# ESP32-Cam-Pico-V1.net
KiCad netlist of a schematic drawn in EAGLE
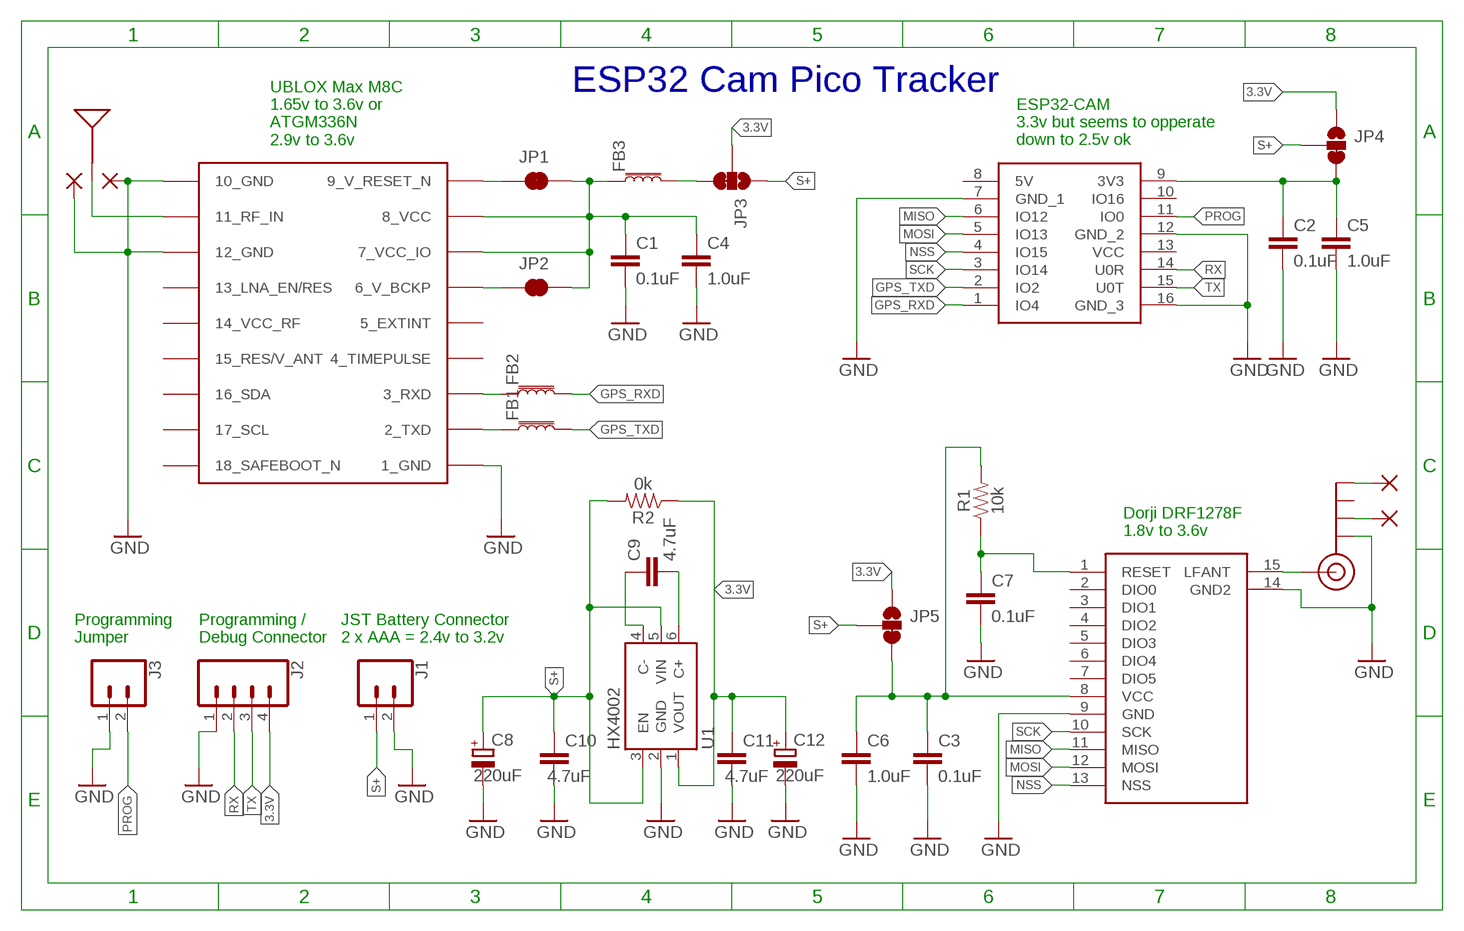
[diagram p0: schematic, sheet 1]

(export (version "E")
  (design (tool "Eeschema 10.0.6"))
  (components
    (comp (ref "C1")
      (value "0.1uF")
      (footprint "eagle-import:0402")
      (libsource (lib "eagle-import") (part "0.1UF-0402-6.3V-10%-X7R"))
    )
    (comp (ref "C2")
      (value "0.1uF")
      (footprint "eagle-import:0402")
      (libsource (lib "eagle-import") (part "0.1UF-0402-6.3V-10%-X7R"))
    )
    (comp (ref "C3")
      (value "0.1uF")
      (footprint "eagle-import:0402")
      (libsource (lib "eagle-import") (part "0.1UF-0402-6.3V-10%-X7R"))
    )
    (comp (ref "C4")
      (value "1.0uF")
      (footprint "eagle-import:0402")
      (libsource (lib "eagle-import") (part "1.0UF-0402-16V-10%"))
    )
    (comp (ref "C5")
      (value "1.0uF")
      (footprint "eagle-import:0402")
      (libsource (lib "eagle-import") (part "1.0UF-0402-16V-10%"))
    )
    (comp (ref "C6")
      (value "1.0uF")
      (footprint "eagle-import:0402")
      (libsource (lib "eagle-import") (part "1.0UF-0402-16V-10%"))
    )
    (comp (ref "C7")
      (value "0.1uF")
      (footprint "eagle-import:0402")
      (libsource (lib "eagle-import") (part "0.1UF-0402-6.3V-10%-X7R"))
    )
    (comp (ref "C8")
      (value "220uF")
      (footprint "eagle-import:SMC_C")
      (libsource (lib "eagle-import") (part "CPOL-EUSMCC"))
    )
    (comp (ref "C9")
      (value "4.7uF")
      (footprint "eagle-import:0402")
      (libsource (lib "eagle-import") (part "1.0UF-0402-16V-10%"))
    )
    (comp (ref "C10")
      (value "4.7uF")
      (footprint "eagle-import:0402")
      (libsource (lib "eagle-import") (part "1.0UF-0402-16V-10%"))
    )
    (comp (ref "C11")
      (value "4.7uF")
      (footprint "eagle-import:0402")
      (libsource (lib "eagle-import") (part "1.0UF-0402-16V-10%"))
    )
    (comp (ref "C12")
      (value "220uF")
      (footprint "eagle-import:SMC_C")
      (libsource (lib "eagle-import") (part "CPOL-EUSMCC"))
    )
    (comp (ref "FB1")
      (value "FERRITE_BEAD-120_OHM-0402")
      (footprint "eagle-import:0402")
      (fields (field (name "MFG_PART") "BLM15HB121SN1D"))
      (libsource (lib "eagle-import") (part "FERRITE_BEAD-120_OHM-0402"))
    )
    (comp (ref "FB2")
      (value "FERRITE_BEAD-120_OHM-0402")
      (footprint "eagle-import:0402")
      (fields (field (name "MFG_PART") "BLM15HB121SN1D"))
      (libsource (lib "eagle-import") (part "FERRITE_BEAD-120_OHM-0402"))
    )
    (comp (ref "FB3")
      (value "FERRITE_BEAD-120_OHM-0402")
      (footprint "eagle-import:0402")
      (fields (field (name "MFG_PART") "BLM15HB121SN1D"))
      (libsource (lib "eagle-import") (part "FERRITE_BEAD-120_OHM-0402"))
    )
    (comp (ref "IC1")
      (value "ESP32-CAM")
      (footprint "eagle-import:ESP32CAM")
      (libsource (lib "eagle-import") (part "ESP32-CAM"))
    )
    (comp (ref "J$1")
      (value "SMA_EDGE")
      (footprint "eagle-import:SMA-EDGE")
      (libsource (lib "eagle-import") (part "SMA_EDGE"))
    )
    (comp (ref "J1")
      (value "CONN_02JST-PTH-2-KIT")
      (footprint "eagle-import:JST-2-PTH-KIT")
      (libsource (lib "eagle-import") (part "CONN_02JST-PTH-2-KIT"))
    )
    (comp (ref "J2")
      (value "CONN_04LOCK")
      (footprint "eagle-import:1X04_LOCK")
      (libsource (lib "eagle-import") (part "CONN_04LOCK"))
    )
    (comp (ref "J3")
      (value "CONN_02LOCK")
      (footprint "eagle-import:1X02_LOCK")
      (libsource (lib "eagle-import") (part "CONN_02LOCK"))
    )
    (comp (ref "JP1")
      (value "JUMPER-SMT_2_NC_TRACE_NO-SILK")
      (footprint "eagle-import:SMT-JUMPER_2_NC_TRACE_NO-SILK")
      (libsource (lib "eagle-import") (part "JUMPER-SMT_2_NC_TRACE_NO-SILK"))
    )
    (comp (ref "JP2")
      (value "JUMPER-SMT_2_NC_TRACE_NO-SILK")
      (footprint "eagle-import:SMT-JUMPER_2_NC_TRACE_NO-SILK")
      (libsource (lib "eagle-import") (part "JUMPER-SMT_2_NC_TRACE_NO-SILK"))
    )
    (comp (ref "JP3")
      (value "JUMPER-SMT_3_1-NC_TRACE_SILK")
      (footprint "eagle-import:SMT-JUMPER_3_1-NC_TRACE_SILK")
      (libsource (lib "eagle-import") (part "JUMPER-SMT_3_1-NC_TRACE_SILK"))
    )
    (comp (ref "JP4")
      (value "JUMPER-SMT_3_1-NC_TRACE_SILK")
      (footprint "eagle-import:SMT-JUMPER_3_1-NC_TRACE_SILK")
      (libsource (lib "eagle-import") (part "JUMPER-SMT_3_1-NC_TRACE_SILK"))
    )
    (comp (ref "JP5")
      (value "JUMPER-SMT_3_1-NC_TRACE_SILK")
      (footprint "eagle-import:SMT-JUMPER_3_1-NC_TRACE_SILK")
      (libsource (lib "eagle-import") (part "JUMPER-SMT_3_1-NC_TRACE_SILK"))
    )
    (comp (ref "PAD1")
      (value "1,6/0,8")
      (footprint "eagle-import:1,6_0,8")
      (libsource (lib "eagle-import") (part "1,6/0,8"))
    )
    (comp (ref "PAD2")
      (value "1,6/0,8")
      (footprint "eagle-import:1,6_0,8")
      (libsource (lib "eagle-import") (part "1,6/0,8"))
    )
    (comp (ref "PAD3")
      (value "1,6/0,8")
      (footprint "eagle-import:1,6_0,8")
      (libsource (lib "eagle-import") (part "1,6/0,8"))
    )
    (comp (ref "PAD4")
      (value "1,6/0,8")
      (footprint "eagle-import:1,6_0,8")
      (libsource (lib "eagle-import") (part "1,6/0,8"))
    )
    (comp (ref "R1")
      (value "10k")
      (footprint "eagle-import:0402")
      (libsource (lib "eagle-import") (part "10KOHM-0402-1/16W-1%"))
    )
    (comp (ref "R2")
      (value "0k")
      (footprint "eagle-import:0402")
      (libsource (lib "eagle-import") (part "10KOHM-0402-1/16W-1%"))
    )
    (comp (ref "U$1")
      (value "MAX-M8")
      (footprint "eagle-import:MAX-M8")
      (libsource (lib "eagle-import") (part "MAX-M8"))
    )
    (comp (ref "U$2")
      (value "1.575GHz")
      (footprint "eagle-import:ANT-GPS-2X7MM")
      (libsource (lib "eagle-import") (part "ANTENNAGPS-2X7MM"))
    )
    (comp (ref "U$3")
      (value "DRF1278F_2")
      (footprint "eagle-import:DRF1278F_2")
      (libsource (lib "eagle-import") (part "DRF1278F_2"))
    )
    (comp (ref "U1")
      (value "HX4002")
      (footprint "eagle-import:SOT23-6")
      (libsource (lib "eagle-import") (part "CE021SOT-23"))
    )
  )
  (nets
    (net (code "1") (name "3.3V") (class "Default")
      (node (ref "C11") (pin "1") (pinfunction "1_1") (pintype "passive"))
      (node (ref "C12") (pin "+") (pinfunction "+_+") (pintype "passive"))
      (node (ref "C2") (pin "1") (pinfunction "1_1") (pintype "passive"))
      (node (ref "C5") (pin "1") (pinfunction "1_1") (pintype "passive"))
      (node (ref "IC1") (pin "9") (pinfunction "3V3_9") (pintype "bidirectional"))
      (node (ref "J2") (pin "4") (pinfunction "4_4") (pintype "passive"))
      (node (ref "JP3") (pin "2") (pinfunction "2_2") (pintype "passive"))
      (node (ref "JP4") (pin "1") (pinfunction "1_1") (pintype "passive"))
      (node (ref "JP4") (pin "3") (pinfunction "3_3") (pintype "passive"))
      (node (ref "JP5") (pin "1") (pinfunction "1_1") (pintype "passive"))
      (node (ref "R2") (pin "1") (pinfunction "1_1") (pintype "passive"))
      (node (ref "U1") (pin "1") (pinfunction "VOUT_1") (pintype "bidirectional"))
    )
    (net (code "2") (name "GND") (class "Default")
      (node (ref "C1") (pin "2") (pinfunction "2_2") (pintype "passive"))
      (node (ref "C10") (pin "2") (pinfunction "2_2") (pintype "passive"))
      (node (ref "C11") (pin "2") (pinfunction "2_2") (pintype "passive"))
      (node (ref "C12") (pin "-") (pinfunction "-_-") (pintype "passive"))
      (node (ref "C2") (pin "2") (pinfunction "2_2") (pintype "passive"))
      (node (ref "C3") (pin "2") (pinfunction "2_2") (pintype "passive"))
      (node (ref "C4") (pin "2") (pinfunction "2_2") (pintype "passive"))
      (node (ref "C5") (pin "2") (pinfunction "2_2") (pintype "passive"))
      (node (ref "C6") (pin "2") (pinfunction "2_2") (pintype "passive"))
      (node (ref "C7") (pin "2") (pinfunction "2_2") (pintype "passive"))
      (node (ref "C8") (pin "-") (pinfunction "-_-") (pintype "passive"))
      (node (ref "IC1") (pin "12") (pinfunction "GND_2_12") (pintype "bidirectional"))
      (node (ref "IC1") (pin "16") (pinfunction "GND_3_16") (pintype "bidirectional"))
      (node (ref "IC1") (pin "7") (pinfunction "GND_1_7") (pintype "bidirectional"))
      (node (ref "J$1") (pin "GND@0") (pinfunction "GND_GND@0") (pintype "bidirectional"))
      (node (ref "J1") (pin "2") (pinfunction "2_2") (pintype "passive"))
      (node (ref "J2") (pin "1") (pinfunction "1_1") (pintype "passive"))
      (node (ref "J3") (pin "1") (pinfunction "1_1") (pintype "passive"))
      (node (ref "PAD1") (pin "1") (pinfunction "P_1") (pintype "passive"))
      (node (ref "PAD2") (pin "1") (pinfunction "P_1") (pintype "passive"))
      (node (ref "U$1") (pin "10_GND") (pinfunction "10_GND_10_GND") (pintype "power_in"))
      (node (ref "U$1") (pin "12_GND") (pinfunction "12_GND_12_GND") (pintype "power_in"))
      (node (ref "U$1") (pin "1_GND") (pinfunction "1_GND_1_GND") (pintype "power_in"))
      (node (ref "U$3") (pin "14") (pinfunction "GND2_14") (pintype "bidirectional"))
      (node (ref "U$3") (pin "9") (pinfunction "GND_9") (pintype "bidirectional"))
      (node (ref "U1") (pin "2") (pinfunction "GND_2") (pintype "bidirectional"))
    )
    (net (code "3") (name "GPS_RXD") (class "Default")
      (node (ref "FB2") (pin "2") (pinfunction "2_2") (pintype "passive"))
      (node (ref "IC1") (pin "1") (pinfunction "IO4_1") (pintype "bidirectional"))
    )
    (net (code "4") (name "GPS_TXD") (class "Default")
      (node (ref "FB1") (pin "2") (pinfunction "2_2") (pintype "passive"))
      (node (ref "IC1") (pin "2") (pinfunction "IO2_2") (pintype "bidirectional"))
    )
    (net (code "5") (name "MISO") (class "Default")
      (node (ref "IC1") (pin "6") (pinfunction "IO12_6") (pintype "bidirectional"))
      (node (ref "U$3") (pin "11") (pinfunction "MISO_11") (pintype "bidirectional"))
    )
    (net (code "6") (name "MOSI") (class "Default")
      (node (ref "IC1") (pin "5") (pinfunction "IO13_5") (pintype "bidirectional"))
      (node (ref "U$3") (pin "12") (pinfunction "MOSI_12") (pintype "bidirectional"))
    )
    (net (code "7") (name "NSS") (class "Default")
      (node (ref "IC1") (pin "4") (pinfunction "IO15_4") (pintype "bidirectional"))
      (node (ref "U$3") (pin "13") (pinfunction "NSS_13") (pintype "bidirectional"))
    )
    (net (code "8") (name "Net-(C1-Pad1)") (class "Default")
      (node (ref "C1") (pin "1") (pinfunction "1_1") (pintype "passive"))
      (node (ref "C4") (pin "1") (pinfunction "1_1") (pintype "passive"))
      (node (ref "FB3") (pin "1") (pinfunction "1_1") (pintype "passive"))
      (node (ref "JP1") (pin "2") (pinfunction "2_2") (pintype "passive"))
      (node (ref "JP2") (pin "2") (pinfunction "2_2") (pintype "passive"))
      (node (ref "U$1") (pin "7_VCC_IO") (pinfunction "7_VCC_IO_7_VCC_IO") (pintype "power_in"))
      (node (ref "U$1") (pin "8_VCC") (pinfunction "8_VCC_8_VCC") (pintype "power_in"))
    )
    (net (code "9") (name "Net-(FB1-Pad1)") (class "Default")
      (node (ref "FB1") (pin "1") (pinfunction "1_1") (pintype "passive"))
      (node (ref "U$1") (pin "2_TXD") (pinfunction "2_TXD_2_TXD") (pintype "bidirectional"))
    )
    (net (code "10") (name "Net-(FB2-Pad1)") (class "Default")
      (node (ref "FB2") (pin "1") (pinfunction "1_1") (pintype "passive"))
      (node (ref "U$1") (pin "3_RXD") (pinfunction "3_RXD_3_RXD") (pintype "bidirectional"))
    )
    (net (code "11") (name "Net-(FB3-Pad2)") (class "Default")
      (node (ref "FB3") (pin "2") (pinfunction "2_2") (pintype "passive"))
      (node (ref "JP3") (pin "3") (pinfunction "3_3") (pintype "passive"))
    )
    (net (code "12") (name "Net-(J$1-SIGNAL)") (class "Default")
      (node (ref "J$1") (pin "SIG") (pinfunction "SIGNAL_SIG") (pintype "bidirectional"))
      (node (ref "U$3") (pin "15") (pinfunction "LFANT_15") (pintype "bidirectional"))
    )
    (net (code "13") (name "Net-(JP2-Pad1)") (class "Default")
      (node (ref "JP2") (pin "1") (pinfunction "1_1") (pintype "passive"))
      (node (ref "U$1") (pin "6_V_BCKP") (pinfunction "6_V_BCKP_6_V_BCKP") (pintype "bidirectional"))
    )
    (net (code "14") (name "Net-(PAD3-P)") (class "Default")
      (node (ref "J$1") (pin "GND@3") (pinfunction "GND_GND@3") (pintype "bidirectional"))
      (node (ref "PAD3") (pin "1") (pinfunction "P_1") (pintype "passive"))
    )
    (net (code "15") (name "Net-(PAD4-P)") (class "Default")
      (node (ref "J$1") (pin "GND@1") (pinfunction "GND_GND@1") (pintype "bidirectional"))
      (node (ref "PAD4") (pin "1") (pinfunction "P_1") (pintype "passive"))
    )
    (net (code "16") (name "Net-(U$1-9_V_RESET_N)") (class "Default")
      (node (ref "JP1") (pin "1") (pinfunction "1_1") (pintype "passive"))
      (node (ref "U$1") (pin "9_RESET_N") (pinfunction "9_V_RESET_N_9_RESET_N") (pintype "power_in"))
    )
    (net (code "17") (name "Net-(U$2-SIGNAL)") (class "Default")
      (node (ref "U$1") (pin "11_RF_IN") (pinfunction "11_RF_IN_11_RF_IN") (pintype "bidirectional"))
      (node (ref "U$2") (pin "1") (pinfunction "SIGNAL_1") (pintype "bidirectional"))
    )
    (net (code "18") (name "Net-(U$3-RESET)") (class "Default")
      (node (ref "C7") (pin "1") (pinfunction "1_1") (pintype "passive"))
      (node (ref "R1") (pin "1") (pinfunction "1_1") (pintype "passive"))
      (node (ref "U$3") (pin "1") (pinfunction "RESET_1") (pintype "bidirectional"))
    )
    (net (code "19") (name "Net-(U1-C+)") (class "Default")
      (node (ref "C9") (pin "2") (pinfunction "2_2") (pintype "passive"))
      (node (ref "U1") (pin "6") (pinfunction "C+_6") (pintype "bidirectional"))
    )
    (net (code "20") (name "Net-(U1-C-)") (class "Default")
      (node (ref "C9") (pin "1") (pinfunction "1_1") (pintype "passive"))
      (node (ref "U1") (pin "4") (pinfunction "C-_4") (pintype "bidirectional"))
    )
    (net (code "21") (name "PROG") (class "Default")
      (node (ref "IC1") (pin "11") (pinfunction "IO0_11") (pintype "bidirectional"))
      (node (ref "J3") (pin "2") (pinfunction "2_2") (pintype "passive"))
    )
    (net (code "22") (name "RX") (class "Default")
      (node (ref "IC1") (pin "14") (pinfunction "U0R_14") (pintype "bidirectional"))
      (node (ref "J2") (pin "2") (pinfunction "2_2") (pintype "passive"))
    )
    (net (code "23") (name "S+") (class "Default")
      (node (ref "C10") (pin "1") (pinfunction "1_1") (pintype "passive"))
      (node (ref "C3") (pin "1") (pinfunction "1_1") (pintype "passive"))
      (node (ref "C6") (pin "1") (pinfunction "1_1") (pintype "passive"))
      (node (ref "C8") (pin "+") (pinfunction "+_+") (pintype "passive"))
      (node (ref "J1") (pin "1") (pinfunction "1_1") (pintype "passive"))
      (node (ref "JP3") (pin "1") (pinfunction "1_1") (pintype "passive"))
      (node (ref "JP4") (pin "2") (pinfunction "2_2") (pintype "passive"))
      (node (ref "JP5") (pin "2") (pinfunction "2_2") (pintype "passive"))
      (node (ref "JP5") (pin "3") (pinfunction "3_3") (pintype "passive"))
      (node (ref "R1") (pin "2") (pinfunction "2_2") (pintype "passive"))
      (node (ref "R2") (pin "2") (pinfunction "2_2") (pintype "passive"))
      (node (ref "U$3") (pin "8") (pinfunction "VCC_8") (pintype "bidirectional"))
      (node (ref "U1") (pin "3") (pinfunction "EN_3") (pintype "bidirectional"))
      (node (ref "U1") (pin "5") (pinfunction "VIN_5") (pintype "bidirectional"))
    )
    (net (code "24") (name "SCK") (class "Default")
      (node (ref "IC1") (pin "3") (pinfunction "IO14_3") (pintype "bidirectional"))
      (node (ref "U$3") (pin "10") (pinfunction "SCK_10") (pintype "bidirectional"))
    )
    (net (code "25") (name "TX") (class "Default")
      (node (ref "IC1") (pin "15") (pinfunction "U0T_15") (pintype "bidirectional"))
      (node (ref "J2") (pin "3") (pinfunction "3_3") (pintype "passive"))
    )
    (net (code "26") (name "unconnected-(IC1-5V-Pad8)") (class "Default")
      (node (ref "IC1") (pin "8") (pinfunction "5V_8") (pintype "bidirectional"))
    )
    (net (code "27") (name "unconnected-(IC1-IO16-Pad10)") (class "Default")
      (node (ref "IC1") (pin "10") (pinfunction "IO16_10") (pintype "bidirectional"))
    )
    (net (code "28") (name "unconnected-(IC1-VCC-Pad13)") (class "Default")
      (node (ref "IC1") (pin "13") (pinfunction "VCC_13") (pintype "bidirectional"))
    )
    (net (code "29") (name "unconnected-(J$1-GND-PadGND@2)") (class "Default")
      (node (ref "J$1") (pin "GND@2") (pinfunction "GND_GND@2") (pintype "bidirectional"))
    )
    (net (code "30") (name "unconnected-(U$1-13_LNA_EN{slash}RES-Pad13_LNA_EN)") (class "Default")
      (node (ref "U$1") (pin "13_LNA_EN") (pinfunction "13_LNA_EN/RES_13_LNA_EN") (pintype "bidirectional"))
    )
    (net (code "31") (name "unconnected-(U$1-15_RES{slash}V_ANT-Pad15_V_ANT{slash}RESERVED)") (class "Default")
      (node (ref "U$1") (pin "15_V_ANT/RESERVED") (pinfunction "15_RES/V_ANT_15_V_ANT/RESERVED") (pintype "bidirectional"))
    )
    (net (code "32") (name "unconnected-(U$1-Pad4_TIMEPULSE)") (class "Default")
      (node (ref "U$1") (pin "4_TIMEPULSE") (pinfunction "4_TIMEPULSE_4_TIMEPULSE") (pintype "bidirectional"))
    )
    (net (code "33") (name "unconnected-(U$1-Pad5_EXTINT)") (class "Default")
      (node (ref "U$1") (pin "5_EXTINT") (pinfunction "5_EXTINT_5_EXTINT") (pintype "bidirectional"))
    )
    (net (code "34") (name "unconnected-(U$1-Pad14_VCC_RF)") (class "Default")
      (node (ref "U$1") (pin "14_VCC_RF") (pinfunction "14_VCC_RF_14_VCC_RF") (pintype "bidirectional"))
    )
    (net (code "35") (name "unconnected-(U$1-Pad16_SDA)") (class "Default")
      (node (ref "U$1") (pin "16_SDA") (pinfunction "16_SDA_16_SDA") (pintype "bidirectional"))
    )
    (net (code "36") (name "unconnected-(U$1-Pad17_SCL)") (class "Default")
      (node (ref "U$1") (pin "17_SCL") (pinfunction "17_SCL_17_SCL") (pintype "bidirectional"))
    )
    (net (code "37") (name "unconnected-(U$1-Pad18_SAFEBOOT_N)") (class "Default")
      (node (ref "U$1") (pin "18_SAFEBOOT_N") (pinfunction "18_SAFEBOOT_N_18_SAFEBOOT_N") (pintype "bidirectional"))
    )
    (net (code "38") (name "unconnected-(U$3-DIO0-Pad2)") (class "Default")
      (node (ref "U$3") (pin "2") (pinfunction "DIO0_2") (pintype "bidirectional"))
    )
    (net (code "39") (name "unconnected-(U$3-DIO1-Pad3)") (class "Default")
      (node (ref "U$3") (pin "3") (pinfunction "DIO1_3") (pintype "bidirectional"))
    )
    (net (code "40") (name "unconnected-(U$3-DIO2-Pad4)") (class "Default")
      (node (ref "U$3") (pin "4") (pinfunction "DIO2_4") (pintype "bidirectional"))
    )
    (net (code "41") (name "unconnected-(U$3-DIO3-Pad5)") (class "Default")
      (node (ref "U$3") (pin "5") (pinfunction "DIO3_5") (pintype "bidirectional"))
    )
    (net (code "42") (name "unconnected-(U$3-DIO4-Pad6)") (class "Default")
      (node (ref "U$3") (pin "6") (pinfunction "DIO4_6") (pintype "bidirectional"))
    )
    (net (code "43") (name "unconnected-(U$3-DIO5-Pad7)") (class "Default")
      (node (ref "U$3") (pin "7") (pinfunction "DIO5_7") (pintype "bidirectional"))
    )
  )
)
